# led5.net
KiCad netlist of a schematic drawn in Altium Designer
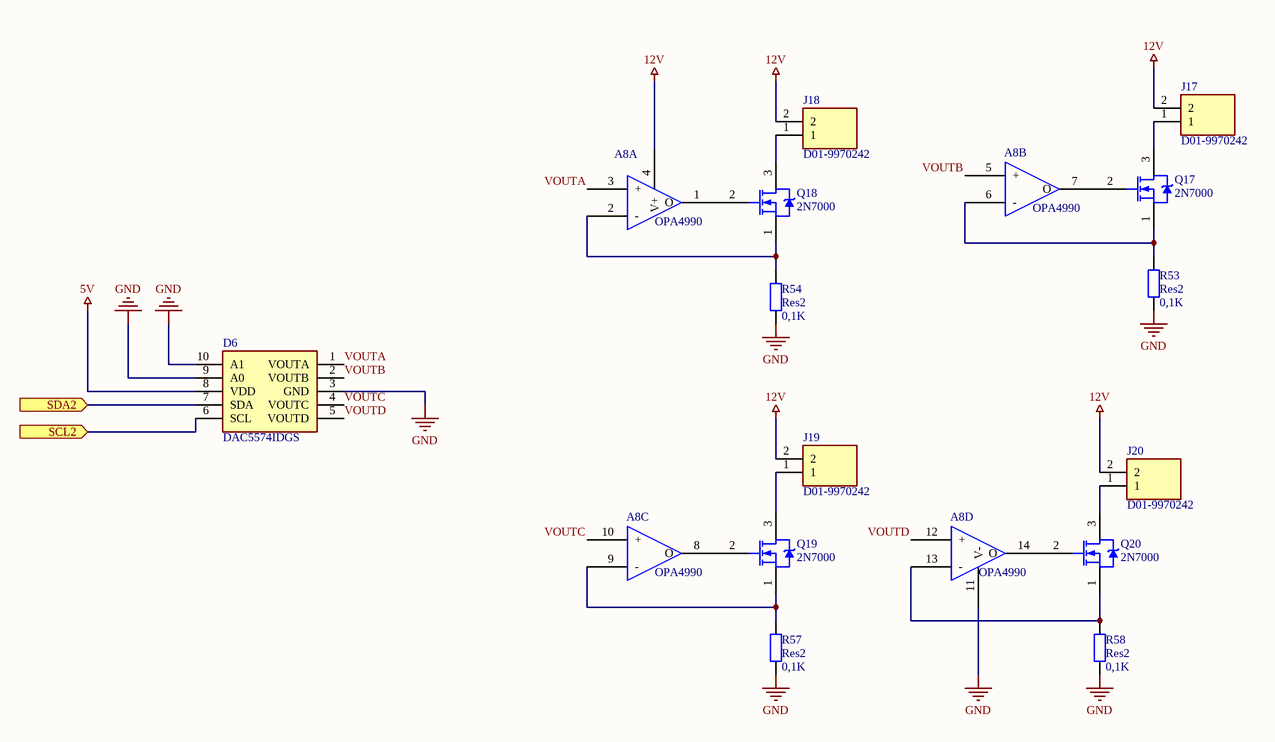
[diagram p0: led5.SchDoc]

(export (version "E")
  (design (tool "Eeschema 10.0.6"))
  (components
    (comp (ref "A8")
      (value "OPA4990")
      (footprint "SOIC127P600X175-14N")
      (libsource (lib "Kalibracija") (part "OPA4990"))
    )
    (comp (ref "D6")
      (value "DAC5574IDGS")
      (footprint "SOP50P490X110-10N")
      (description "Integrated Circuit")
      (fields
        (field (name "MOUSER PART NUMBER") "595-DAC5574IDGS")
        (field (name "RS PART NUMBER") "6621533P")
      )
      (libsource (lib "*") (part "DAC5574IDGS"))
    )
    (comp (ref "J17")
      (value "D01-9970242")
      (footprint "HDR1X2")
      (description "Connector")
      (fields (field (name "MOUSER PART NUMBER") "855-D01-9970242"))
      (libsource (lib "SamacSys2") (part "D01-9970242"))
    )
    (comp (ref "J18")
      (value "D01-9970242")
      (footprint "HDR1X2")
      (description "Connector")
      (fields (field (name "MOUSER PART NUMBER") "855-D01-9970242"))
      (libsource (lib "SamacSys2") (part "D01-9970242"))
    )
    (comp (ref "J19")
      (value "D01-9970242")
      (footprint "HDR1X2")
      (description "Connector")
      (fields (field (name "MOUSER PART NUMBER") "855-D01-9970242"))
      (libsource (lib "SamacSys2") (part "D01-9970242"))
    )
    (comp (ref "J20")
      (value "D01-9970242")
      (footprint "HDR1X2")
      (description "Connector")
      (fields (field (name "MOUSER PART NUMBER") "855-D01-9970242"))
      (libsource (lib "SamacSys2") (part "D01-9970242"))
    )
    (comp (ref "Q17")
      (value "2N7000")
      (footprint "ONSC-TO-92-3-29-11")
      (description "Small Signal MOSFET, 200 mA, 60 V, N-Channel, 3-Pin TO-92, Bulk Box")
      (fields (field (name "MANUFACTURER") "On Semiconductor"))
      (libsource (lib "Components - 24.04.20 - 07.58") (part "CMP-1058-00936-1"))
    )
    (comp (ref "Q18")
      (value "2N7000")
      (footprint "ONSC-TO-92-3-29-11")
      (description "Small Signal MOSFET, 200 mA, 60 V, N-Channel, 3-Pin TO-92, Bulk Box")
      (fields (field (name "MANUFACTURER") "On Semiconductor"))
      (libsource (lib "Components - 24.04.20 - 07.58") (part "CMP-1058-00936-1"))
    )
    (comp (ref "Q19")
      (value "2N7000")
      (footprint "ONSC-TO-92-3-29-11")
      (description "Small Signal MOSFET, 200 mA, 60 V, N-Channel, 3-Pin TO-92, Bulk Box")
      (fields (field (name "MANUFACTURER") "On Semiconductor"))
      (libsource (lib "Components - 24.04.20 - 07.58") (part "CMP-1058-00936-1"))
    )
    (comp (ref "Q20")
      (value "2N7000")
      (footprint "ONSC-TO-92-3-29-11")
      (description "Small Signal MOSFET, 200 mA, 60 V, N-Channel, 3-Pin TO-92, Bulk Box")
      (fields (field (name "MANUFACTURER") "On Semiconductor"))
      (libsource (lib "Components - 24.04.20 - 07.58") (part "CMP-1058-00936-1"))
    )
    (comp (ref "R53")
      (value "Res2")
      (footprint "C1210")
      (description "Resistor")
      (fields (field (name "ALTIUM_VALUE") "0,1K") (field (name "PUBLISHER") "Altium Limited"))
      (libsource (lib "Miscellaneous Devices") (part "Res2"))
    )
    (comp (ref "R54")
      (value "Res2")
      (footprint "C1210")
      (description "Resistor")
      (fields (field (name "ALTIUM_VALUE") "0,1K") (field (name "PUBLISHER") "Altium Limited"))
      (libsource (lib "Miscellaneous Devices") (part "Res2"))
    )
    (comp (ref "R57")
      (value "Res2")
      (footprint "C1210")
      (description "Resistor")
      (fields (field (name "ALTIUM_VALUE") "0,1K") (field (name "PUBLISHER") "Altium Limited"))
      (libsource (lib "Miscellaneous Devices") (part "Res2"))
    )
    (comp (ref "R58")
      (value "Res2")
      (footprint "C1210")
      (description "Resistor")
      (fields (field (name "ALTIUM_VALUE") "0,1K") (field (name "PUBLISHER") "Altium Limited"))
      (libsource (lib "Miscellaneous Devices") (part "Res2"))
    )
  )
  (nets
    (net (code "1") (name "/SCL2") (class "Default")
      (node (ref "D6") (pin "6") (pinfunction "SCL_6") (pintype "passive"))
    )
    (net (code "2") (name "/SDA2") (class "Default")
      (node (ref "D6") (pin "7") (pinfunction "SDA_7") (pintype "passive"))
    )
    (net (code "3") (name "/VOUTA") (class "Default")
      (node (ref "A8") (pin "3") (pinfunction "+_3") (pintype "passive"))
      (node (ref "D6") (pin "1") (pinfunction "VOUTA_1") (pintype "passive"))
    )
    (net (code "4") (name "/VOUTB") (class "Default")
      (node (ref "A8") (pin "5") (pinfunction "+_5") (pintype "passive"))
      (node (ref "D6") (pin "2") (pinfunction "VOUTB_2") (pintype "passive"))
    )
    (net (code "5") (name "/VOUTC") (class "Default")
      (node (ref "A8") (pin "10") (pinfunction "+_10") (pintype "passive"))
      (node (ref "D6") (pin "4") (pinfunction "VOUTC_4") (pintype "passive"))
    )
    (net (code "6") (name "/VOUTD") (class "Default")
      (node (ref "A8") (pin "12") (pinfunction "+_12") (pintype "passive"))
      (node (ref "D6") (pin "5") (pinfunction "VOUTD_5") (pintype "passive"))
    )
    (net (code "7") (name "5V") (class "Default")
      (node (ref "D6") (pin "8") (pinfunction "VDD_8") (pintype "passive"))
    )
    (net (code "8") (name "12V") (class "Default")
      (node (ref "A8") (pin "4") (pinfunction "V+_4") (pintype "power_in"))
      (node (ref "J17") (pin "2") (pinfunction "2_2") (pintype "passive"))
      (node (ref "J18") (pin "2") (pinfunction "2_2") (pintype "passive"))
      (node (ref "J19") (pin "2") (pinfunction "2_2") (pintype "passive"))
      (node (ref "J20") (pin "2") (pinfunction "2_2") (pintype "passive"))
    )
    (net (code "9") (name "GND") (class "Default")
      (node (ref "A8") (pin "11") (pinfunction "V-_11") (pintype "power_in"))
      (node (ref "D6") (pin "10") (pinfunction "A1_10") (pintype "passive"))
      (node (ref "D6") (pin "3") (pinfunction "GND_3") (pintype "passive"))
      (node (ref "D6") (pin "9") (pinfunction "A0_9") (pintype "passive"))
      (node (ref "R53") (pin "1") (pinfunction "1_1") (pintype "passive"))
      (node (ref "R54") (pin "1") (pinfunction "1_1") (pintype "passive"))
      (node (ref "R57") (pin "1") (pinfunction "1_1") (pintype "passive"))
      (node (ref "R58") (pin "1") (pinfunction "1_1") (pintype "passive"))
    )
    (net (code "10") (name "Net-(A8A--)") (class "Default")
      (node (ref "A8") (pin "2") (pinfunction "-_2") (pintype "passive"))
      (node (ref "Q18") (pin "1") (pinfunction "S_1") (pintype "passive"))
      (node (ref "R54") (pin "2") (pinfunction "2_2") (pintype "passive"))
    )
    (net (code "11") (name "Net-(A8A-O)") (class "Default")
      (node (ref "A8") (pin "1") (pinfunction "O_1") (pintype "passive"))
      (node (ref "Q18") (pin "2") (pinfunction "G_2") (pintype "passive"))
    )
    (net (code "12") (name "Net-(A8B--)") (class "Default")
      (node (ref "A8") (pin "6") (pinfunction "-_6") (pintype "passive"))
      (node (ref "Q17") (pin "1") (pinfunction "S_1") (pintype "passive"))
      (node (ref "R53") (pin "2") (pinfunction "2_2") (pintype "passive"))
    )
    (net (code "13") (name "Net-(A8B-O)") (class "Default")
      (node (ref "A8") (pin "7") (pinfunction "O_7") (pintype "passive"))
      (node (ref "Q17") (pin "2") (pinfunction "G_2") (pintype "passive"))
    )
    (net (code "14") (name "Net-(A8C--)") (class "Default")
      (node (ref "A8") (pin "9") (pinfunction "-_9") (pintype "passive"))
      (node (ref "Q19") (pin "1") (pinfunction "S_1") (pintype "passive"))
      (node (ref "R57") (pin "2") (pinfunction "2_2") (pintype "passive"))
    )
    (net (code "15") (name "Net-(A8C-O)") (class "Default")
      (node (ref "A8") (pin "8") (pinfunction "O_8") (pintype "passive"))
      (node (ref "Q19") (pin "2") (pinfunction "G_2") (pintype "passive"))
    )
    (net (code "16") (name "Net-(A8D--)") (class "Default")
      (node (ref "A8") (pin "13") (pinfunction "-_13") (pintype "passive"))
      (node (ref "Q20") (pin "1") (pinfunction "S_1") (pintype "passive"))
      (node (ref "R58") (pin "2") (pinfunction "2_2") (pintype "passive"))
    )
    (net (code "17") (name "Net-(A8D-O)") (class "Default")
      (node (ref "A8") (pin "14") (pinfunction "O_14") (pintype "passive"))
      (node (ref "Q20") (pin "2") (pinfunction "G_2") (pintype "passive"))
    )
    (net (code "18") (name "Net-(Q17-D)") (class "Default")
      (node (ref "J17") (pin "1") (pinfunction "1_1") (pintype "passive"))
      (node (ref "Q17") (pin "3") (pinfunction "D_3") (pintype "passive"))
    )
    (net (code "19") (name "Net-(Q18-D)") (class "Default")
      (node (ref "J18") (pin "1") (pinfunction "1_1") (pintype "passive"))
      (node (ref "Q18") (pin "3") (pinfunction "D_3") (pintype "passive"))
    )
    (net (code "20") (name "Net-(Q19-D)") (class "Default")
      (node (ref "J19") (pin "1") (pinfunction "1_1") (pintype "passive"))
      (node (ref "Q19") (pin "3") (pinfunction "D_3") (pintype "passive"))
    )
    (net (code "21") (name "Net-(Q20-D)") (class "Default")
      (node (ref "J20") (pin "1") (pinfunction "1_1") (pintype "passive"))
      (node (ref "Q20") (pin "3") (pinfunction "D_3") (pintype "passive"))
    )
  )
)
